# 02-MCU.net
KiCad netlist of a schematic drawn in Altium Designer
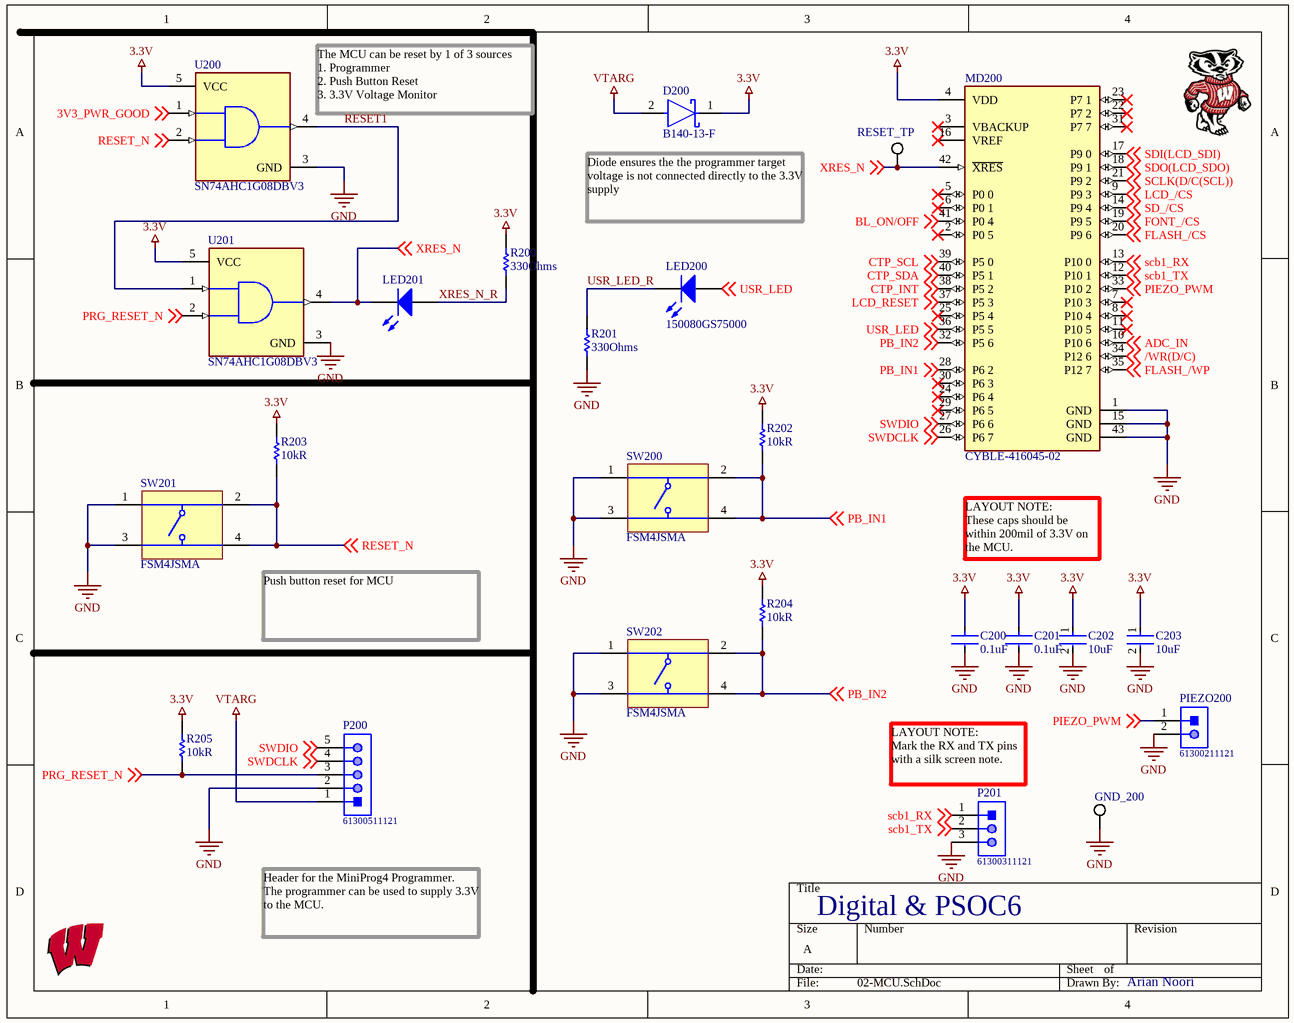
[diagram p0: 02-MCU.SchDoc]

(export (version "E")
  (design (tool "Eeschema 10.0.6"))
  (components
    (comp (ref "C200")
      (value "0.1uF")
      (footprint "FP-CL21-IPC_C")
      (description "CL21 Series 0805 100nF 50V ±10% Tolerance X7R Multilayer Ceramic Chip Capacitor")
      (fields (field (name "TOLERANCE") "10%") (field (name "VOLTAGE") "50V"))
      (libsource (lib "Altium Content Vault") (part "b4654b650e69147ec39a6b967a45e02"))
    )
    (comp (ref "C201")
      (value "0.1uF")
      (footprint "FP-CL21-IPC_C")
      (description "CL21 Series 0805 100nF 50V ±10% Tolerance X7R Multilayer Ceramic Chip Capacitor")
      (fields (field (name "TOLERANCE") "10%") (field (name "VOLTAGE") "50V"))
      (libsource (lib "Altium Content Vault") (part "b4654b650e69147ec39a6b967a45e02"))
    )
    (comp (ref "C202")
      (value "10uF")
      (footprint "FP-C0805C-DG-MFG")
      (description "CAP CER 10UF 10V X5R 0805")
      (fields (field (name "TOLERANCE") "10%") (field (name "MANUFACTURER PART NUMBER") "C0805C106K8PACTU"))
      (libsource (lib "Altium Content Vault") (part "11868f565c42a9108669ba33697ecf6"))
    )
    (comp (ref "C203")
      (value "10uF")
      (footprint "FP-C0805C-DG-MFG")
      (description "CAP CER 10UF 10V X5R 0805")
      (fields (field (name "TOLERANCE") "10%") (field (name "MANUFACTURER PART NUMBER") "C0805C106K8PACTU"))
      (libsource (lib "Altium Content Vault") (part "11868f565c42a9108669ba33697ecf6"))
    )
    (comp (ref "D200")
      (value "B140-13-F")
      (footprint "FP-SMA-MFG")
      (description "DIODE SCHOTTKY 40V 1A SMA")
      (libsource (lib "Altium Content Vault") (part "1d6ec82d83fb6aee721767c19dac4b9"))
    )
    (comp (ref "GND_200")
      (value "5019")
      (footprint "KSTN-5019_V")
      (description "Test Point, 1 Position SMD, RoHS, Tape and Reel")
      (libsource (lib "Altium Content Vault") (part "TESTPOINT_WHITE"))
    )
    (comp (ref "LED200")
      (value "150080GS75000")
      (footprint "0805_A")
      (description "SMD mono-color Chip LED, WL-SMCW, Green")
      (fields (field (name "MANUFACTURER") "Wuerth Elektronik"))
      (libsource (lib "Altium Content Vault") (part "WE-LED_K1A2-2"))
    )
    (comp (ref "LED201")
      (value "150080RS75000")
      (footprint "0805_A")
      (description "SMD mono-color Chip LED, WL-SMCW, Red")
      (fields (field (name "MANUFACTURER") "Wuerth Elektronik"))
      (libsource (lib "Altium Content Vault") (part "WE-LED_K1A2-2"))
    )
    (comp (ref "MD200")
      (value "CYBLE-416045-02")
      (footprint "FP-CYBLE-416045-02-MFG")
      (description "RF TXRX MOD BLUETOOTH TRACE ANT")
      (fields
        (field (name "OCTOPART") "https://octopart.com/cyble-416045-02-cypress+semiconductor-96386825")
        (field (name "MANUFACTURER") "Cypress Semiconductor")
      )
      (libsource (lib "Altium Content Vault") (part "10a29a4e77099fbb6f911efb04878b1"))
    )
    (comp (ref "P200")
      (value "61300511121")
      (footprint "61300511121")
      (description "THT Vertical Pin Header WR-PHD, Pitch 2.54 mm, Single Row, 5 pins")
      (fields (field (name "MANUFACTURER") "Wurth Elektronik") (field (name "PUBLISHER") "WurthElektronik"))
      (libsource (lib "Altium Content Vault") (part "WE-CN-1P-M-R5"))
    )
    (comp (ref "P201")
      (value "61300311121")
      (footprint "61300311121")
      (description "CONN HEADER 3 POS 2.54")
      (fields (field (name "MANUFACTURER") "Wurth Elektronik") (field (name "PUBLISHER") "WurthElektronik"))
      (libsource (lib "Altium Content Vault") (part "WE-CN-1P-M-R3"))
    )
    (comp (ref "PIEZO200")
      (value "61300211121")
      (footprint "61300211121")
      (description "THT Vertical Pin Header WR-PHD, Pitch 2.54 mm, Single Row, 2 pins")
      (fields (field (name "MANUFACTURER") "Wurth Elektronik") (field (name "PUBLISHER") "WurthElektronik"))
      (libsource (lib "Altium Content Vault") (part "WE-CN-1P-M-R2"))
    )
    (comp (ref "R200")
      (value "RC0805FR-07330RL")
      (footprint "RESC2013X60X35LL10T20")
      (description "Chip Resistor, 330 Ohm, +/- 1%, 125 mW, -55 to 155 degC, 0805 (2012 Metric), RoHS, Tape and Reel")
      (fields
        (field (name "MANUFACTURER") "Yageo")
        (field (name "TOLERANCE") "1%")
        (field (name "RESISTANCE") "330Ohms")
      )
      (libsource (lib "Altium Content Vault") (part "RES-2"))
    )
    (comp (ref "R201")
      (value "RC0805FR-07330RL")
      (footprint "RESC2013X60X35LL10T20")
      (description "Chip Resistor, 330 Ohm, +/- 1%, 125 mW, -55 to 155 degC, 0805 (2012 Metric), RoHS, Tape and Reel")
      (fields
        (field (name "MANUFACTURER") "Yageo")
        (field (name "TOLERANCE") "1%")
        (field (name "RESISTANCE") "330Ohms")
      )
      (libsource (lib "Altium Content Vault") (part "RES-2"))
    )
    (comp (ref "R202")
      (value "RC0805FR-0710KL")
      (footprint "RESC2013X60X35NL10T20")
      (description "Chip Resistor, 10 KOhm, +/- 1%, 0.125 W, -55 to 155 degC, 0805 (2012 Metric), RoHS, Tape and Reel")
      (fields
        (field (name "MANUFACTURER") "Yageo")
        (field (name "RESISTANCE") "10kR")
        (field (name "TOLERANCE") "1%")
      )
      (libsource (lib "Altium Content Vault") (part "RES-2"))
    )
    (comp (ref "R203")
      (value "RC0805FR-0710KL")
      (footprint "RESC2013X60X35NL10T20")
      (description "Chip Resistor, 10 KOhm, +/- 1%, 0.125 W, -55 to 155 degC, 0805 (2012 Metric), RoHS, Tape and Reel")
      (fields
        (field (name "MANUFACTURER") "Yageo")
        (field (name "RESISTANCE") "10kR")
        (field (name "TOLERANCE") "1%")
      )
      (libsource (lib "Altium Content Vault") (part "RES-2"))
    )
    (comp (ref "R204")
      (value "RC0805FR-0710KL")
      (footprint "RESC2013X60X35NL10T20")
      (description "Chip Resistor, 10 KOhm, +/- 1%, 0.125 W, -55 to 155 degC, 0805 (2012 Metric), RoHS, Tape and Reel")
      (fields
        (field (name "MANUFACTURER") "Yageo")
        (field (name "RESISTANCE") "10kR")
        (field (name "TOLERANCE") "1%")
      )
      (libsource (lib "Altium Content Vault") (part "RES-2"))
    )
    (comp (ref "R205")
      (value "RC0805FR-0710KL")
      (footprint "RESC2013X60X35NL10T20")
      (description "Chip Resistor, 10 KOhm, +/- 1%, 0.125 W, -55 to 155 degC, 0805 (2012 Metric), RoHS, Tape and Reel")
      (fields
        (field (name "MANUFACTURER") "Yageo")
        (field (name "RESISTANCE") "10kR")
        (field (name "TOLERANCE") "1%")
      )
      (libsource (lib "Altium Content Vault") (part "RES-2"))
    )
    (comp (ref "RESET_TP")
      (value "5019")
      (footprint "KSTN-5019_V")
      (description "Test Point, 1 Position SMD, RoHS, Tape and Reel")
      (libsource (lib "Altium Content Vault") (part "TESTPOINT_WHITE"))
    )
    (comp (ref "SW200")
      (value "FSM4JSMA")
      (footprint "TECO-FSM4JSMA_V")
      (description "Swicth, SPST, 24 V, -35 to 85 degC, 4-Pin SMD, RoHS, Tape and Reel")
      (fields (field (name "MANUFACTURER") "TE Connectivity"))
      (libsource (lib "Altium Content Vault") (part "SW-SPST-4_A"))
    )
    (comp (ref "SW201")
      (value "FSM4JSMA")
      (footprint "TECO-FSM4JSMA_V")
      (description "Swicth, SPST, 24 V, -35 to 85 degC, 4-Pin SMD, RoHS, Tape and Reel")
      (fields (field (name "MANUFACTURER") "TE Connectivity"))
      (libsource (lib "Altium Content Vault") (part "SW-SPST-4_A"))
    )
    (comp (ref "SW202")
      (value "FSM4JSMA")
      (footprint "TECO-FSM4JSMA_V")
      (description "Swicth, SPST, 24 V, -35 to 85 degC, 4-Pin SMD, RoHS, Tape and Reel")
      (fields (field (name "MANUFACTURER") "TE Connectivity"))
      (libsource (lib "Altium Content Vault") (part "SW-SPST-4_A"))
    )
    (comp (ref "U200")
      (value "SN74AHC1G08DBV3")
      (footprint "FP-DBV0005A-IPC_C")
      (description "IC GATE AND 1CH 2-INP SOT23-5")
      (libsource (lib "Altium Content Vault") (part "675e79b427d6219a5295bf943425e1c"))
    )
    (comp (ref "U201")
      (value "SN74AHC1G08DBV3")
      (footprint "FP-DBV0005A-IPC_C")
      (description "IC GATE AND 1CH 2-INP SOT23-5")
      (libsource (lib "Altium Content Vault") (part "675e79b427d6219a5295bf943425e1c"))
    )
  )
  (nets
    (net (code "1") (name "/RESET1") (class "Default")
      (node (ref "U200") (pin "4") (pinfunction "Y_4") (pintype "output"))
      (node (ref "U201") (pin "1") (pinfunction "A_1") (pintype "input"))
    )
    (net (code "2") (name "/USR_LED_R") (class "Default")
      (node (ref "LED200") (pin "1") (pinfunction "K_1") (pintype "passive"))
      (node (ref "R201") (pin "2") (pinfunction "2_2") (pintype "passive"))
    )
    (net (code "3") (name "/XRES_N_R") (class "Default")
      (node (ref "LED201") (pin "2") (pinfunction "A_2") (pintype "passive"))
      (node (ref "R200") (pin "1") (pinfunction "1_1") (pintype "passive"))
    )
    (net (code "4") (name "3.3V") (class "Default")
      (node (ref "C200") (pin "1") (pinfunction "1_1") (pintype "passive"))
      (node (ref "C201") (pin "1") (pinfunction "1_1") (pintype "passive"))
      (node (ref "C202") (pin "1") (pinfunction "1_1") (pintype "passive"))
      (node (ref "C203") (pin "1") (pinfunction "1_1") (pintype "passive"))
      (node (ref "D200") (pin "1") (pinfunction "C_1") (pintype "passive"))
      (node (ref "MD200") (pin "4") (pinfunction "VDD_4") (pintype "power_in"))
      (node (ref "R200") (pin "2") (pinfunction "2_2") (pintype "passive"))
      (node (ref "R202") (pin "2") (pinfunction "2_2") (pintype "passive"))
      (node (ref "R203") (pin "2") (pinfunction "2_2") (pintype "passive"))
      (node (ref "R204") (pin "2") (pinfunction "2_2") (pintype "passive"))
      (node (ref "R205") (pin "2") (pinfunction "2_2") (pintype "passive"))
      (node (ref "U200") (pin "5") (pinfunction "VCC_5") (pintype "power_in"))
      (node (ref "U201") (pin "5") (pinfunction "VCC_5") (pintype "power_in"))
    )
    (net (code "5") (name "3V3_PWR_GOOD") (class "Default")
      (node (ref "U200") (pin "1") (pinfunction "A_1") (pintype "input"))
    )
    (net (code "6") (name "ADC_IN") (class "Default")
      (node (ref "MD200") (pin "10") (pinfunction "P10_6_10") (pintype "bidirectional"))
    )
    (net (code "7") (name "BL_ON{slash}OFF") (class "Default")
      (node (ref "MD200") (pin "41") (pinfunction "P0_4_41") (pintype "bidirectional"))
    )
    (net (code "8") (name "CTP_INT") (class "Default")
      (node (ref "MD200") (pin "38") (pinfunction "P5_2_38") (pintype "bidirectional"))
    )
    (net (code "9") (name "CTP_SCL") (class "Default")
      (node (ref "MD200") (pin "39") (pinfunction "P5_0_39") (pintype "bidirectional"))
    )
    (net (code "10") (name "CTP_SDA") (class "Default")
      (node (ref "MD200") (pin "40") (pinfunction "P5_1_40") (pintype "bidirectional"))
    )
    (net (code "11") (name "FLASH_{slash}CS") (class "Default")
      (node (ref "MD200") (pin "20") (pinfunction "P9_6_20") (pintype "bidirectional"))
    )
    (net (code "12") (name "FLASH_{slash}WP") (class "Default")
      (node (ref "MD200") (pin "35") (pinfunction "P12_7_35") (pintype "bidirectional"))
    )
    (net (code "13") (name "FONT_{slash}CS") (class "Default")
      (node (ref "MD200") (pin "19") (pinfunction "P9_5_19") (pintype "bidirectional"))
    )
    (net (code "14") (name "GND") (class "Default")
      (node (ref "C200") (pin "2") (pinfunction "2_2") (pintype "passive"))
      (node (ref "C201") (pin "2") (pinfunction "2_2") (pintype "passive"))
      (node (ref "C202") (pin "2") (pinfunction "2_2") (pintype "passive"))
      (node (ref "C203") (pin "2") (pinfunction "2_2") (pintype "passive"))
      (node (ref "GND_200") (pin "1") (pinfunction "1_1") (pintype "passive"))
      (node (ref "MD200") (pin "1") (pinfunction "GND_1") (pintype "power_in"))
      (node (ref "MD200") (pin "15") (pinfunction "GND_15") (pintype "power_in"))
      (node (ref "MD200") (pin "43") (pinfunction "GND_43") (pintype "power_in"))
      (node (ref "P200") (pin "2") (pinfunction "2_2") (pintype "passive"))
      (node (ref "P201") (pin "3") (pinfunction "3_3") (pintype "passive"))
      (node (ref "PIEZO200") (pin "2") (pinfunction "2_2") (pintype "passive"))
      (node (ref "R201") (pin "1") (pinfunction "1_1") (pintype "passive"))
      (node (ref "SW200") (pin "1") (pinfunction "1_1") (pintype "passive"))
      (node (ref "SW200") (pin "3") (pinfunction "3_3") (pintype "passive"))
      (node (ref "SW201") (pin "1") (pinfunction "1_1") (pintype "passive"))
      (node (ref "SW201") (pin "3") (pinfunction "3_3") (pintype "passive"))
      (node (ref "SW202") (pin "1") (pinfunction "1_1") (pintype "passive"))
      (node (ref "SW202") (pin "3") (pinfunction "3_3") (pintype "passive"))
      (node (ref "U200") (pin "3") (pinfunction "GND_3") (pintype "power_in"))
      (node (ref "U201") (pin "3") (pinfunction "GND_3") (pintype "power_in"))
    )
    (net (code "15") (name "LCD_RESET") (class "Default")
      (node (ref "MD200") (pin "37") (pinfunction "P5_3_37") (pintype "bidirectional"))
    )
    (net (code "16") (name "LCD_{slash}CS") (class "Default")
      (node (ref "MD200") (pin "9") (pinfunction "P9_3_9") (pintype "bidirectional"))
    )
    (net (code "17") (name "PB_IN1") (class "Default")
      (node (ref "MD200") (pin "28") (pinfunction "P6_2_28") (pintype "bidirectional"))
      (node (ref "R202") (pin "1") (pinfunction "1_1") (pintype "passive"))
      (node (ref "SW200") (pin "2") (pinfunction "2_2") (pintype "passive"))
      (node (ref "SW200") (pin "4") (pinfunction "4_4") (pintype "passive"))
    )
    (net (code "18") (name "PB_IN2") (class "Default")
      (node (ref "MD200") (pin "32") (pinfunction "P5_6_32") (pintype "bidirectional"))
      (node (ref "R204") (pin "1") (pinfunction "1_1") (pintype "passive"))
      (node (ref "SW202") (pin "2") (pinfunction "2_2") (pintype "passive"))
      (node (ref "SW202") (pin "4") (pinfunction "4_4") (pintype "passive"))
    )
    (net (code "19") (name "PIEZO_PWM") (class "Default")
      (node (ref "MD200") (pin "33") (pinfunction "P10_2_33") (pintype "bidirectional"))
      (node (ref "PIEZO200") (pin "1") (pinfunction "1_1") (pintype "passive"))
    )
    (net (code "20") (name "PRG_RESET_N") (class "Default")
      (node (ref "P200") (pin "3") (pinfunction "3_3") (pintype "passive"))
      (node (ref "R205") (pin "1") (pinfunction "1_1") (pintype "passive"))
      (node (ref "U201") (pin "2") (pinfunction "B_2") (pintype "input"))
    )
    (net (code "21") (name "RESET_N") (class "Default")
      (node (ref "R203") (pin "1") (pinfunction "1_1") (pintype "passive"))
      (node (ref "SW201") (pin "2") (pinfunction "2_2") (pintype "passive"))
      (node (ref "SW201") (pin "4") (pinfunction "4_4") (pintype "passive"))
      (node (ref "U200") (pin "2") (pinfunction "B_2") (pintype "input"))
    )
    (net (code "22") (name "SCLK(D{slash}C(SCL))") (class "Default")
      (node (ref "MD200") (pin "21") (pinfunction "P9_2_21") (pintype "bidirectional"))
    )
    (net (code "23") (name "SDI(LCD_SDI)") (class "Default")
      (node (ref "MD200") (pin "17") (pinfunction "P9_0_17") (pintype "bidirectional"))
    )
    (net (code "24") (name "SDO(LCD_SDO)") (class "Default")
      (node (ref "MD200") (pin "18") (pinfunction "P9_1_18") (pintype "bidirectional"))
    )
    (net (code "25") (name "SD_{slash}CS") (class "Default")
      (node (ref "MD200") (pin "14") (pinfunction "P9_4_14") (pintype "bidirectional"))
    )
    (net (code "26") (name "SWDCLK") (class "Default")
      (node (ref "MD200") (pin "26") (pinfunction "P6_7_26") (pintype "bidirectional"))
      (node (ref "P200") (pin "4") (pinfunction "4_4") (pintype "passive"))
    )
    (net (code "27") (name "SWDIO") (class "Default")
      (node (ref "MD200") (pin "27") (pinfunction "P6_6_27") (pintype "bidirectional"))
      (node (ref "P200") (pin "5") (pinfunction "5_5") (pintype "passive"))
    )
    (net (code "28") (name "USR_LED") (class "Default")
      (node (ref "LED200") (pin "2") (pinfunction "A_2") (pintype "passive"))
      (node (ref "MD200") (pin "36") (pinfunction "P5_5_36") (pintype "bidirectional"))
    )
    (net (code "29") (name "VTARG") (class "Default")
      (node (ref "D200") (pin "2") (pinfunction "A_2") (pintype "passive"))
      (node (ref "P200") (pin "1") (pinfunction "1_1") (pintype "passive"))
    )
    (net (code "30") (name "XRES_N") (class "Default")
      (node (ref "LED201") (pin "1") (pinfunction "K_1") (pintype "passive"))
      (node (ref "MD200") (pin "42") (pinfunction "~{XRES}_42") (pintype "input"))
      (node (ref "RESET_TP") (pin "1") (pinfunction "1_1") (pintype "passive"))
      (node (ref "U201") (pin "4") (pinfunction "Y_4") (pintype "output"))
    )
    (net (code "31") (name "scb1_RX") (class "Default")
      (node (ref "MD200") (pin "13") (pinfunction "P10_0_13") (pintype "bidirectional"))
      (node (ref "P201") (pin "1") (pinfunction "1_1") (pintype "passive"))
    )
    (net (code "32") (name "scb1_TX") (class "Default")
      (node (ref "MD200") (pin "12") (pinfunction "P10_1_12") (pintype "bidirectional"))
      (node (ref "P201") (pin "2") (pinfunction "2_2") (pintype "passive"))
    )
    (net (code "33") (name "unconnected-(MD200-P0_0-Pad5)") (class "Default")
      (node (ref "MD200") (pin "5") (pinfunction "P0_0_5") (pintype "bidirectional+no_connect"))
    )
    (net (code "34") (name "unconnected-(MD200-P0_1-Pad6)") (class "Default")
      (node (ref "MD200") (pin "6") (pinfunction "P0_1_6") (pintype "bidirectional+no_connect"))
    )
    (net (code "35") (name "unconnected-(MD200-P0_5-Pad2)") (class "Default")
      (node (ref "MD200") (pin "2") (pinfunction "P0_5_2") (pintype "bidirectional+no_connect"))
    )
    (net (code "36") (name "unconnected-(MD200-P5_4-Pad25)") (class "Default")
      (node (ref "MD200") (pin "25") (pinfunction "P5_4_25") (pintype "bidirectional+no_connect"))
    )
    (net (code "37") (name "unconnected-(MD200-P6_3-Pad30)") (class "Default")
      (node (ref "MD200") (pin "30") (pinfunction "P6_3_30") (pintype "bidirectional+no_connect"))
    )
    (net (code "38") (name "unconnected-(MD200-P6_4-Pad24)") (class "Default")
      (node (ref "MD200") (pin "24") (pinfunction "P6_4_24") (pintype "bidirectional+no_connect"))
    )
    (net (code "39") (name "unconnected-(MD200-P6_5-Pad29)") (class "Default")
      (node (ref "MD200") (pin "29") (pinfunction "P6_5_29") (pintype "bidirectional+no_connect"))
    )
    (net (code "40") (name "unconnected-(MD200-P7_1-Pad23)") (class "Default")
      (node (ref "MD200") (pin "23") (pinfunction "P7_1_23") (pintype "bidirectional+no_connect"))
    )
    (net (code "41") (name "unconnected-(MD200-P7_2-Pad22)") (class "Default")
      (node (ref "MD200") (pin "22") (pinfunction "P7_2_22") (pintype "bidirectional+no_connect"))
    )
    (net (code "42") (name "unconnected-(MD200-P7_7-Pad31)") (class "Default")
      (node (ref "MD200") (pin "31") (pinfunction "P7_7_31") (pintype "bidirectional+no_connect"))
    )
    (net (code "43") (name "unconnected-(MD200-P10_3-Pad7)") (class "Default")
      (node (ref "MD200") (pin "7") (pinfunction "P10_3_7") (pintype "bidirectional+no_connect"))
    )
    (net (code "44") (name "unconnected-(MD200-P10_4-Pad8)") (class "Default")
      (node (ref "MD200") (pin "8") (pinfunction "P10_4_8") (pintype "bidirectional+no_connect"))
    )
    (net (code "45") (name "unconnected-(MD200-P10_5-Pad11)") (class "Default")
      (node (ref "MD200") (pin "11") (pinfunction "P10_5_11") (pintype "bidirectional+no_connect"))
    )
    (net (code "46") (name "unconnected-(MD200-VBACKUP-Pad3)") (class "Default")
      (node (ref "MD200") (pin "3") (pinfunction "VBACKUP_3") (pintype "power_in+no_connect"))
    )
    (net (code "47") (name "unconnected-(MD200-VREF-Pad16)") (class "Default")
      (node (ref "MD200") (pin "16") (pinfunction "VREF_16") (pintype "power_in+no_connect"))
    )
    (net (code "48") (name "{slash}WR(D{slash}C)") (class "Default")
      (node (ref "MD200") (pin "34") (pinfunction "P12_6_34") (pintype "bidirectional"))
    )
  )
)
